# SCH_Single-Sprayer_TH_2025-12-06.net
KiCad netlist of a schematic drawn in EasyEDA
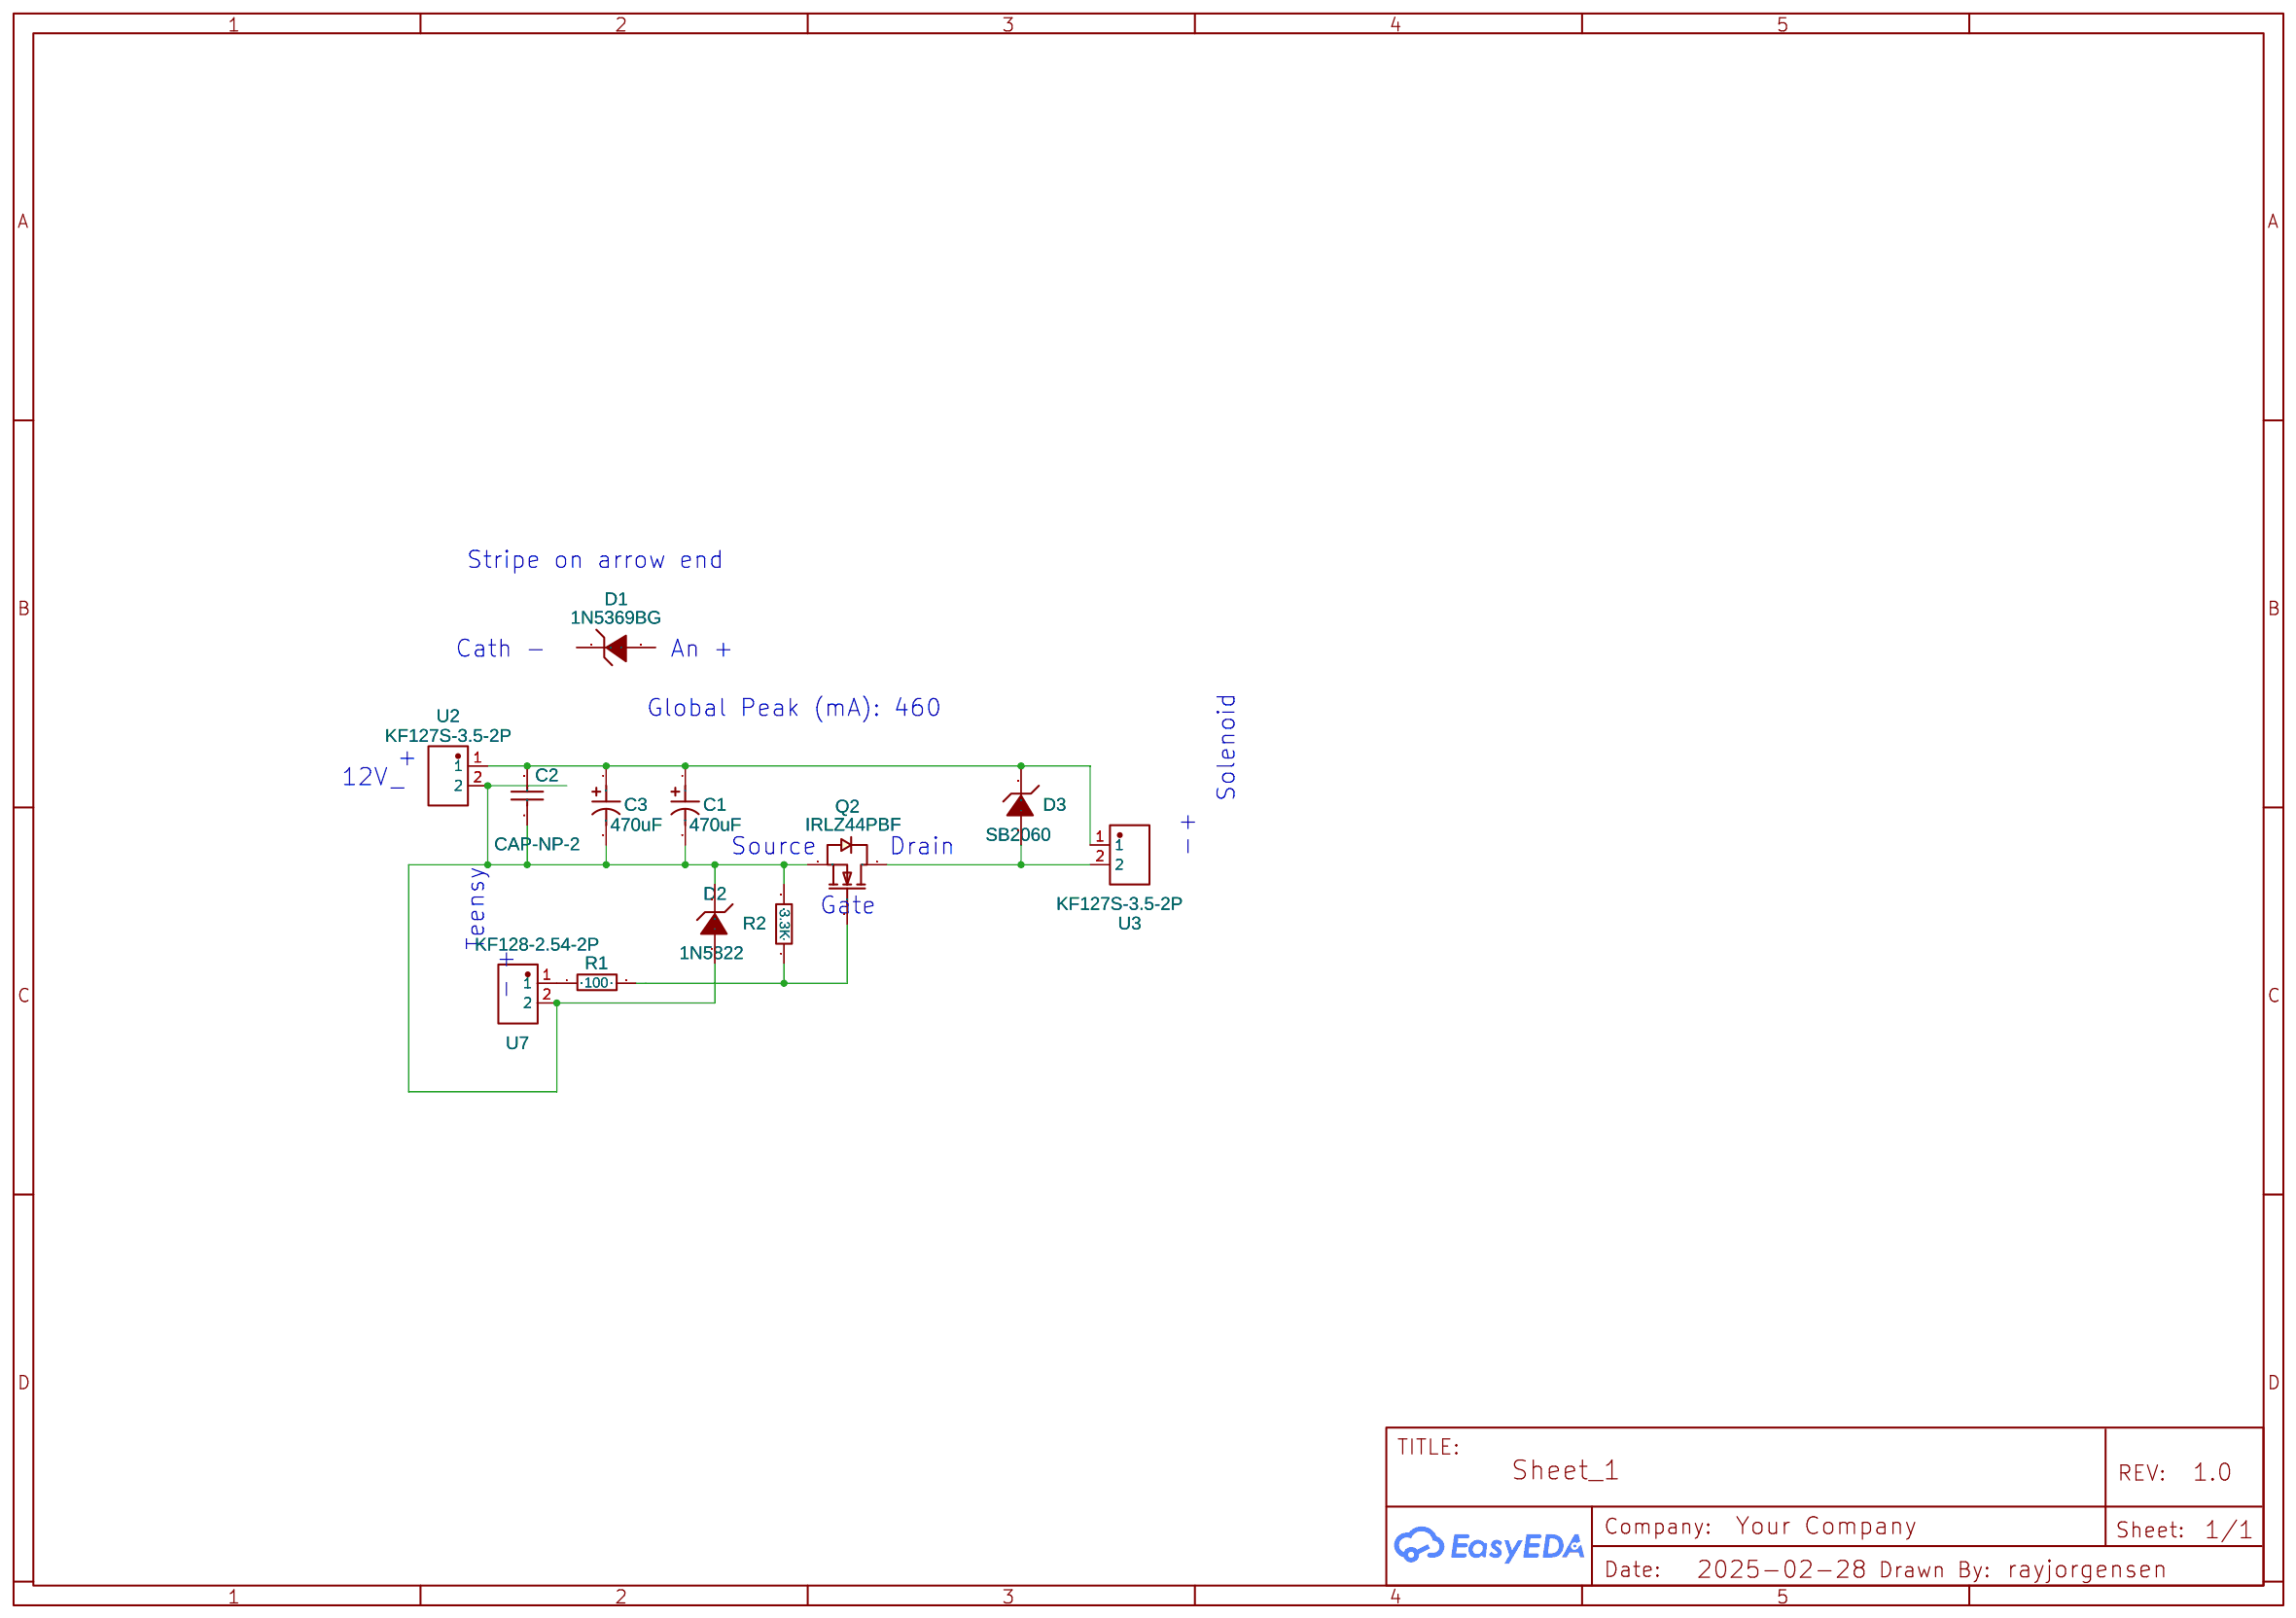
[diagram p0: schematic sheet]

(export (version "E")
  (design (tool "Eeschema 10.0.6"))
  (components
    (comp (ref "C1")
      (value "470uF")
      (fields
        (field (name "Manufacturer Part") "UHE1E102MHD6TO")
        (field (name "Manufacturer") "Nichicon(尼吉康)")
      )
      (libsource (lib "") (part "UHE1E102MHD6TO"))
    )
    (comp (ref "C2")
      (value "CAP-NP-2")
      (fields (field (name "Manufacturer") "Vishay"))
      (libsource (lib "") (part "CAP-NP-2"))
    )
    (comp (ref "C3")
      (value "470uF")
      (fields
        (field (name "Manufacturer Part") "UHE1E102MHD6TO")
        (field (name "Manufacturer") "Nichicon(尼吉康)")
      )
      (libsource (lib "") (part "UHE1E102MHD6TO"))
    )
    (comp (ref "D1")
      (value "1N5369BG")
      (fields (field (name "Manufacturer") "onsemi(安森美)"))
      (libsource (lib "") (part "1N5369BG"))
    )
    (comp (ref "D2")
      (value "1N5822")
      (fields (field (name "Manufacturer Part") "1N5369BG") (field (name "Manufacturer") "onsemi(安森美)"))
      (libsource (lib "") (part "1N5369BG_1"))
    )
    (comp (ref "D3")
      (value "SB2060")
      (fields (field (name "Manufacturer Part") "1N5369BG") (field (name "Manufacturer") "onsemi(安森美)"))
      (libsource (lib "") (part "1N5369BG_1"))
    )
    (comp (ref "Q2")
      (value "IRLZ44PBF")
      (fields (field (name "Manufacturer Part") "IRFZ44NPBF") (field (name "Manufacturer") "Infineon(英飞凌)"))
      (libsource (lib "") (part "IRFZ44NPBF"))
    )
    (comp (ref "R1")
      (value "100")
      (fields (field (name "Manufacturer Part") "MFR0W4F6803A50") (field (name "Manufacturer") "UniOhm"))
      (libsource (lib "") (part "MFR0W4F6803A50"))
    )
    (comp (ref "R2")
      (value "3.3K")
      (fields (field (name "Manufacturer Part") "MFR0W4F6803A50") (field (name "Manufacturer") "UniOhm"))
      (libsource (lib "") (part "MFR0W4F6803A50_1"))
    )
    (comp (ref "U2")
      (value "KF127S-3.5-2P")
      (fields (field (name "Manufacturer") "KEFA(科发)"))
      (libsource (lib "") (part "KF127S-3.5-2P"))
    )
    (comp (ref "U3")
      (value "KF127S-3.5-2P")
      (fields (field (name "Manufacturer") "KEFA(科发)"))
      (libsource (lib "") (part "KF127S-3.5-2P_1"))
    )
    (comp (ref "U7")
      (value "KF128-2.54-2P")
      (fields (field (name "Manufacturer") "Cixi Kefa Elec"))
      (libsource (lib "") (part "KF128-2.54-2P"))
    )
  )
  (nets
    (net (code "1") (name "Net-(D2-A)") (class "Default")
      (node (ref "C1") (pin "2") (pinfunction "2_2") (pintype "input"))
      (node (ref "C2") (pin "2") (pinfunction "2_2") (pintype "unspecified"))
      (node (ref "C3") (pin "2") (pinfunction "2_2") (pintype "input"))
      (node (ref "D2") (pin "1") (pinfunction "C_1") (pintype "unspecified"))
      (node (ref "D2") (pin "2") (pinfunction "A_2") (pintype "unspecified"))
      (node (ref "Q2") (pin "3") (pinfunction "S_3") (pintype "unspecified"))
      (node (ref "R2") (pin "2") (pinfunction "2_2") (pintype "input"))
      (node (ref "U2") (pin "2") (pinfunction "2_2") (pintype "unspecified"))
      (node (ref "U7") (pin "2") (pinfunction "2_2") (pintype "unspecified"))
    )
    (net (code "2") (name "Net-(D3-A)") (class "Default")
      (node (ref "D3") (pin "2") (pinfunction "A_2") (pintype "unspecified"))
      (node (ref "Q2") (pin "2") (pinfunction "D_2") (pintype "unspecified"))
      (node (ref "U3") (pin "2") (pinfunction "2_2") (pintype "unspecified"))
    )
    (net (code "3") (name "Net-(D3-C)") (class "Default")
      (node (ref "C1") (pin "1") (pinfunction "1_1") (pintype "input"))
      (node (ref "C2") (pin "1") (pinfunction "1_1") (pintype "unspecified"))
      (node (ref "C3") (pin "1") (pinfunction "1_1") (pintype "input"))
      (node (ref "D3") (pin "1") (pinfunction "C_1") (pintype "unspecified"))
      (node (ref "U2") (pin "1") (pinfunction "1_1") (pintype "unspecified"))
      (node (ref "U3") (pin "1") (pinfunction "1_1") (pintype "unspecified"))
    )
    (net (code "4") (name "Net-(Q2-G)") (class "Default")
      (node (ref "Q2") (pin "1") (pinfunction "G_1") (pintype "unspecified"))
      (node (ref "R1") (pin "2") (pinfunction "2_2") (pintype "input"))
      (node (ref "R2") (pin "1") (pinfunction "1_1") (pintype "input"))
    )
    (net (code "5") (name "Net-(R1-Pad1)") (class "Default")
      (node (ref "R1") (pin "1") (pinfunction "1_1") (pintype "input"))
      (node (ref "U7") (pin "1") (pinfunction "1_1") (pintype "unspecified"))
    )
    (net (code "6") (name "unconnected-(D1-A-Pad2)") (class "Default")
      (node (ref "D1") (pin "2") (pinfunction "A_2") (pintype "unspecified"))
    )
    (net (code "7") (name "unconnected-(D1-C-Pad1)") (class "Default")
      (node (ref "D1") (pin "1") (pinfunction "C_1") (pintype "unspecified"))
    )
  )
)
